# adapter.net
KiCad netlist of a schematic drawn in Altium Designer
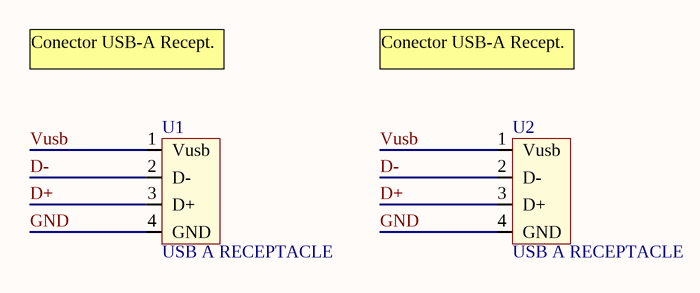
[diagram p0: adapter.SchDoc]

(export (version "E")
  (design (tool "Eeschema 10.0.6"))
  (components
    (comp (ref "U1")
      (value "USB A RECEPTACLE")
      (footprint "USB A RECEPTACLE THD")
      (libsource (lib "uMote") (part "USB A RECEPTACLE"))
    )
    (comp (ref "U2")
      (value "USB A RECEPTACLE")
      (footprint "USB A RECEPTACLE THD")
      (libsource (lib "uMote") (part "USB A RECEPTACLE"))
    )
  )
  (nets
    (net (code "1") (name "/D+") (class "Default")
      (node (ref "U1") (pin "3") (pinfunction "D+_3") (pintype "passive"))
      (node (ref "U2") (pin "3") (pinfunction "D+_3") (pintype "passive"))
    )
    (net (code "2") (name "/D-") (class "Default")
      (node (ref "U1") (pin "2") (pinfunction "D-_2") (pintype "passive"))
      (node (ref "U2") (pin "2") (pinfunction "D-_2") (pintype "passive"))
    )
    (net (code "3") (name "/GND") (class "Default")
      (node (ref "U1") (pin "4") (pinfunction "GND_4") (pintype "passive"))
      (node (ref "U2") (pin "4") (pinfunction "GND_4") (pintype "passive"))
    )
    (net (code "4") (name "/Vusb") (class "Default")
      (node (ref "U1") (pin "1") (pinfunction "Vusb_1") (pintype "passive"))
      (node (ref "U2") (pin "1") (pinfunction "Vusb_1") (pintype "passive"))
    )
  )
)
